# 3_power.net
KiCad netlist of a schematic drawn in Altium Designer
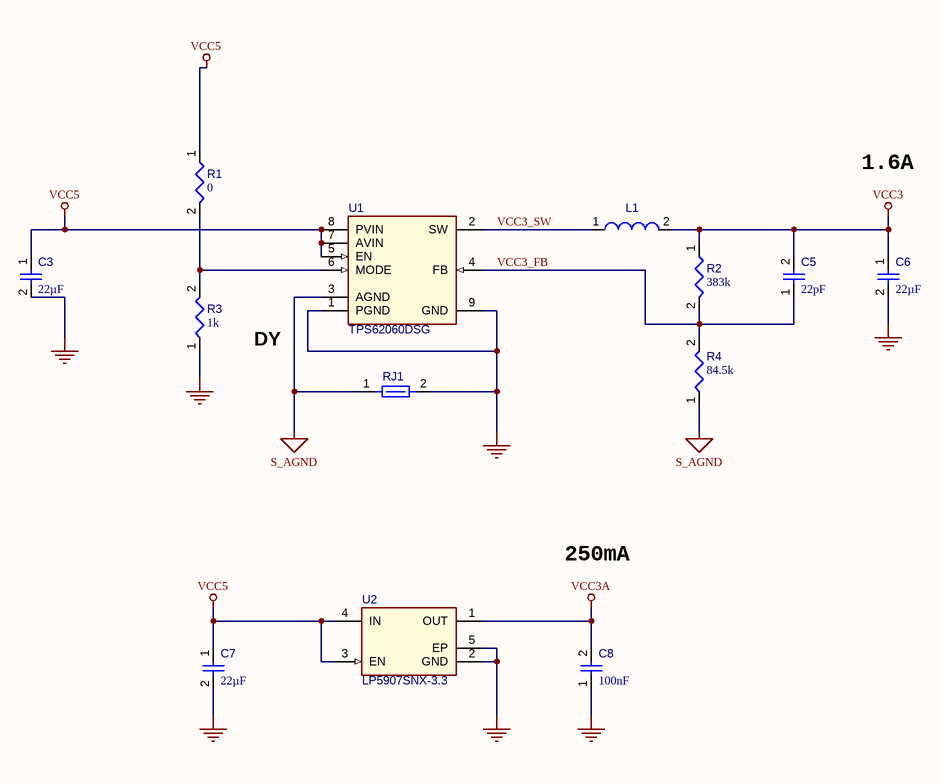
[diagram p0: 3_power.SchDoc]

(export (version "E")
  (design (tool "Eeschema 10.0.6"))
  (components
    (comp (ref "C3")
      (value "22µF")
      (footprint "CAPC0805(2012)145_L")
      (description "Chip Capacitor, 22µF +/-40%, 16V, 0805, Thickness 1.45 mm")
      (fields (field (name "TOLERANCE") "5%") (field (name "Comment") "Capacitor 22µF +/-40% 16V 0805"))
      (libsource (lib "SKA- Automa玢o de Engenharias") (part "CAP-NP-2"))
    )
    (comp (ref "C5")
      (value "22pF")
      (footprint "CAPC0402(1005)60_L")
      (description "Chip Capacitor, 22pF +/-10%, 50V, 0402, Thickness 0.6 mm")
      (fields (field (name "TOLERANCE") "10%") (field (name "Comment") "Capacitor 22pF +/-10% 50V 0402"))
      (libsource (lib "SKA- Automa玢o de Engenharias") (part "CAP-NP-2"))
    )
    (comp (ref "C6")
      (value "22µF")
      (footprint "CAPC0805(2012)145_L")
      (description "Chip Capacitor, 22µF +/-40%, 16V, 0805, Thickness 1.45 mm")
      (fields (field (name "TOLERANCE") "5%") (field (name "Comment") "Capacitor 22µF +/-40% 16V 0805"))
      (libsource (lib "SKA- Automa玢o de Engenharias") (part "CAP-NP-2"))
    )
    (comp (ref "C7")
      (value "22µF")
      (footprint "CAPC0805(2012)145_L")
      (description "Chip Capacitor, 22µF +/-40%, 16V, 0805, Thickness 1.45 mm")
      (fields (field (name "TOLERANCE") "5%") (field (name "Comment") "Capacitor 22µF +/-40% 16V 0805"))
      (libsource (lib "SKA- Automa玢o de Engenharias") (part "CAP-NP-2"))
    )
    (comp (ref "C8")
      (value "100nF")
      (footprint "CAPC0402(1005)60_L")
      (description "Chip Capacitor, 100nF +/-20%, 10V, 0402, Thickness 0.6 mm")
      (fields (field (name "TOLERANCE") "20%") (field (name "Comment") "Capacitor 100nF +/-20% 10V 0402"))
      (libsource (lib "SKA- Automa玢o de Engenharias") (part "CAP-NP-2"))
    )
    (comp (ref "L1")
      (value "VLS252010HBX-2R2M-1")
      (footprint "TDK-VLS252010_V")
      (description "Inductor for Power Circuit, 2.2 uH, +/- 20%, -40 to 105 degC, 2-Pin SMD, RoHS, Tape and Reel")
      (fields (field (name "TOLERANCE") "20%"))
      (libsource (lib "SKA- Automa玢o de Engenharias") (part "CMP-001-0020-1"))
    )
    (comp (ref "R1")
      (value "0")
      (footprint "RESC0402(1005)_L")
      (description "Jumper 0402")
      (libsource (lib "SKA- Automa玢o de Engenharias") (part "RES-2"))
    )
    (comp (ref "R2")
      (value "383k")
      (footprint "RESC0402(1005)_L")
      (description "Chip Resistor, 383 kOhms, +/-1 %, 63 mW, -55 to 155 degC, 0402")
      (fields (field (name "TOLERANCE") "1%") (field (name "POWER") "63mW"))
      (libsource (lib "SKA- Automa玢o de Engenharias") (part "RES-2"))
    )
    (comp (ref "R3")
      (value "1k")
      (footprint "RESC0402(1005)_L")
      (description "Chip Resistor, 1 kOhms, +/-5 %, 63 mW, -55 to 155 degC, 0402")
      (fields (field (name "TOLERANCE") "5%") (field (name "POWER") "63mW"))
      (libsource (lib "SKA- Automa玢o de Engenharias") (part "RES-2"))
    )
    (comp (ref "R4")
      (value "84.5k")
      (footprint "RESC0402(1005)_L")
      (description "Chip Resistor, 84,5 kOhms, +/-1 %, 63 mW, -55 to 155 degC, 0402")
      (fields (field (name "TOLERANCE") "1%") (field (name "POWER") "63mW"))
      (libsource (lib "SKA- Automa玢o de Engenharias") (part "RES-2"))
    )
    (comp (ref "RJ1")
      (value "Net Tie 10x8mil")
      (footprint "New footprint 1")
      (libsource (lib "<Company> Server") (part "CMP-00022-00002-2"))
    )
    (comp (ref "U1")
      (value "TPS62060DSG")
      (footprint "DSG0008A_V")
      (description "Step Down Converter, 3 MHz, 1.6 A, -45 to 85 degC, 8-Pin WSON, RoHS, Tape and Reel")
      (libsource (lib "<Company> Server") (part "CMP-00002-13_2"))
    )
    (comp (ref "U2")
      (value "LP5907SNX-3.3")
      (footprint "TI-DQN4-480X480TP_V")
      (description "Ultra-Low-Noise, Low-IQ LDO, 3.3 V, 0.25 A, -40 to 125 degC, 4-Pin X2SON, RoHS, Tape and Reel")
      (libsource (lib "SKA- Automa玢o de Engenharias") (part "CMP-00094-7"))
    )
  )
  (nets
    (net (code "1") (name "/VCC3_FB") (class "Default")
      (node (ref "C5") (pin "1") (pinfunction "1_1") (pintype "passive"))
      (node (ref "R2") (pin "2") (pinfunction "2_2") (pintype "passive"))
      (node (ref "R4") (pin "2") (pinfunction "2_2") (pintype "passive"))
      (node (ref "U1") (pin "4") (pinfunction "FB_4") (pintype "input"))
    )
    (net (code "2") (name "/VCC3_SW") (class "Default")
      (node (ref "L1") (pin "1") (pinfunction "1_1") (pintype "passive"))
      (node (ref "U1") (pin "2") (pinfunction "SW_2") (pintype "power_in"))
    )
    (net (code "3") (name "GND") (class "Default")
      (node (ref "C3") (pin "2") (pinfunction "2_2") (pintype "passive"))
      (node (ref "C6") (pin "2") (pinfunction "2_2") (pintype "passive"))
      (node (ref "C7") (pin "2") (pinfunction "2_2") (pintype "passive"))
      (node (ref "C8") (pin "1") (pinfunction "1_1") (pintype "passive"))
      (node (ref "R3") (pin "1") (pinfunction "1_1") (pintype "passive"))
      (node (ref "RJ1") (pin "2") (pinfunction "2_2") (pintype "passive"))
      (node (ref "U1") (pin "1") (pinfunction "PGND_1") (pintype "power_in"))
      (node (ref "U1") (pin "9") (pinfunction "GND_9") (pintype "power_in"))
      (node (ref "U2") (pin "2") (pinfunction "GND_2") (pintype "power_in"))
      (node (ref "U2") (pin "5") (pinfunction "EP_5") (pintype "power_in"))
    )
    (net (code "4") (name "Net-(U1-MODE)") (class "Default")
      (node (ref "R1") (pin "2") (pinfunction "2_2") (pintype "passive"))
      (node (ref "R3") (pin "2") (pinfunction "2_2") (pintype "passive"))
      (node (ref "U1") (pin "6") (pinfunction "MODE_6") (pintype "input"))
    )
    (net (code "5") (name "S_AGND") (class "Default")
      (node (ref "R4") (pin "1") (pinfunction "1_1") (pintype "passive"))
      (node (ref "RJ1") (pin "1") (pinfunction "1_1") (pintype "passive"))
      (node (ref "U1") (pin "3") (pinfunction "AGND_3") (pintype "power_in"))
    )
    (net (code "6") (name "VCC3") (class "Default")
      (node (ref "C5") (pin "2") (pinfunction "2_2") (pintype "passive"))
      (node (ref "C6") (pin "1") (pinfunction "1_1") (pintype "passive"))
      (node (ref "L1") (pin "2") (pinfunction "2_2") (pintype "passive"))
      (node (ref "R2") (pin "1") (pinfunction "1_1") (pintype "passive"))
    )
    (net (code "7") (name "VCC3A") (class "Default")
      (node (ref "C8") (pin "2") (pinfunction "2_2") (pintype "passive"))
      (node (ref "U2") (pin "1") (pinfunction "OUT_1") (pintype "power_in"))
    )
    (net (code "8") (name "VCC5") (class "Default")
      (node (ref "C3") (pin "1") (pinfunction "1_1") (pintype "passive"))
      (node (ref "C7") (pin "1") (pinfunction "1_1") (pintype "passive"))
      (node (ref "R1") (pin "1") (pinfunction "1_1") (pintype "passive"))
      (node (ref "U1") (pin "5") (pinfunction "EN_5") (pintype "input"))
      (node (ref "U1") (pin "7") (pinfunction "AVIN_7") (pintype "power_in"))
      (node (ref "U1") (pin "8") (pinfunction "PVIN_8") (pintype "power_in"))
      (node (ref "U2") (pin "3") (pinfunction "EN_3") (pintype "input"))
      (node (ref "U2") (pin "4") (pinfunction "IN_4") (pintype "power_in"))
    )
  )
)
